# audio_io.net
KiCad netlist of a schematic drawn in Altium Designer
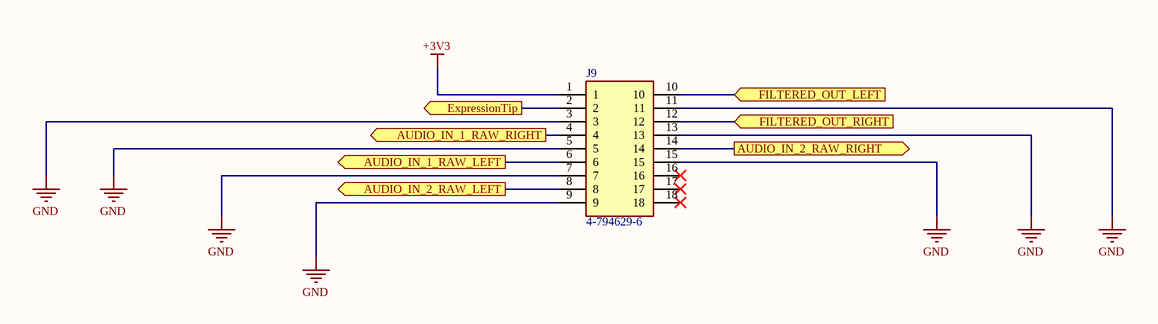
[diagram p0: audio_io.SchDoc]

(export (version "E")
  (design (tool "Eeschema 10.0.6"))
  (components
    (comp (ref "J9")
      (value "4-794629-6")
      (footprint "audio_dev_pcb:47946296")
      (description "Connector")
      (fields (field (name "MOUSER PART NUMBER") "571-4-794629-6"))
      (libsource (lib "*") (part "4-794629-6"))
    )
  )
  (nets
    (net (code "1") (name "+3V3") (class "Default")
      (node (ref "J9") (pin "1") (pinfunction "1_1") (pintype "passive"))
    )
    (net (code "2") (name "/AUDIO_IN_1_RAW_LEFT") (class "Default")
      (node (ref "J9") (pin "6") (pinfunction "6_6") (pintype "passive"))
    )
    (net (code "3") (name "/AUDIO_IN_1_RAW_RIGHT") (class "Default")
      (node (ref "J9") (pin "4") (pinfunction "4_4") (pintype "passive"))
    )
    (net (code "4") (name "/AUDIO_IN_2_RAW_LEFT") (class "Default")
      (node (ref "J9") (pin "8") (pinfunction "8_8") (pintype "passive"))
    )
    (net (code "5") (name "/AUDIO_IN_2_RAW_RIGHT") (class "Default")
      (node (ref "J9") (pin "14") (pinfunction "14_14") (pintype "passive"))
    )
    (net (code "6") (name "/ExpressionTip") (class "Default")
      (node (ref "J9") (pin "2") (pinfunction "2_2") (pintype "passive"))
    )
    (net (code "7") (name "/FILTERED_OUT_LEFT") (class "Default")
      (node (ref "J9") (pin "10") (pinfunction "10_10") (pintype "passive"))
    )
    (net (code "8") (name "/FILTERED_OUT_RIGHT") (class "Default")
      (node (ref "J9") (pin "12") (pinfunction "12_12") (pintype "passive"))
    )
    (net (code "9") (name "GND") (class "Default")
      (node (ref "J9") (pin "11") (pinfunction "11_11") (pintype "passive"))
      (node (ref "J9") (pin "13") (pinfunction "13_13") (pintype "passive"))
      (node (ref "J9") (pin "15") (pinfunction "15_15") (pintype "passive"))
      (node (ref "J9") (pin "3") (pinfunction "3_3") (pintype "passive"))
      (node (ref "J9") (pin "5") (pinfunction "5_5") (pintype "passive"))
      (node (ref "J9") (pin "7") (pinfunction "7_7") (pintype "passive"))
      (node (ref "J9") (pin "9") (pinfunction "9_9") (pintype "passive"))
    )
    (net (code "10") (name "unconnected-(J9-Pad16)") (class "Default")
      (node (ref "J9") (pin "16") (pinfunction "16_16") (pintype "passive+no_connect"))
    )
    (net (code "11") (name "unconnected-(J9-Pad17)") (class "Default")
      (node (ref "J9") (pin "17") (pinfunction "17_17") (pintype "passive+no_connect"))
    )
    (net (code "12") (name "unconnected-(J9-Pad18)") (class "Default")
      (node (ref "J9") (pin "18") (pinfunction "18_18") (pintype "passive+no_connect"))
    )
  )
)
